# ultra-low-noise-psu-pos-v0001.net
KiCad netlist of a schematic drawn in EAGLE
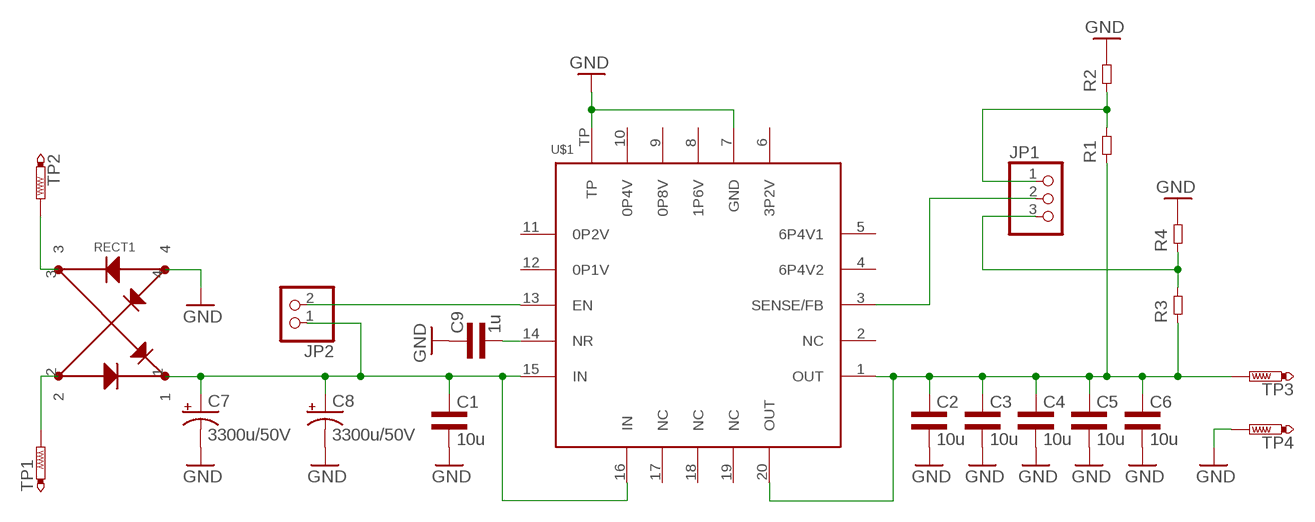
[diagram p0: schematic, sheet 1]

(export (version "E")
  (design (tool "Eeschema 10.0.6"))
  (components
    (comp (ref "C1")
      (value "10u")
      (footprint "eagle-import:0805L3")
      (libsource (lib "eagle-import") (part "CAP0805L3"))
    )
    (comp (ref "C2")
      (value "10u")
      (footprint "eagle-import:0805L3")
      (libsource (lib "eagle-import") (part "CAP0805L3"))
    )
    (comp (ref "C3")
      (value "10u")
      (footprint "eagle-import:0805L3")
      (libsource (lib "eagle-import") (part "CAP0805L3"))
    )
    (comp (ref "C4")
      (value "10u")
      (footprint "eagle-import:0805L3")
      (libsource (lib "eagle-import") (part "CAP0805L3"))
    )
    (comp (ref "C5")
      (value "10u")
      (footprint "eagle-import:0805L3")
      (libsource (lib "eagle-import") (part "CAP0805L3"))
    )
    (comp (ref "C6")
      (value "10u")
      (footprint "eagle-import:0805L3")
      (libsource (lib "eagle-import") (part "CAP0805L3"))
    )
    (comp (ref "C7")
      (value "3300u/50V")
      (footprint "eagle-import:E7,5-18")
      (libsource (lib "eagle-import") (part "CPOL-USE7.5-18"))
    )
    (comp (ref "C8")
      (value "3300u/50V")
      (footprint "eagle-import:E7,5-18")
      (libsource (lib "eagle-import") (part "CPOL-USE7.5-18"))
    )
    (comp (ref "C9")
      (value "1u")
      (footprint "eagle-import:0603L3")
      (libsource (lib "eagle-import") (part "CAP0603L3"))
    )
    (comp (ref "JP1")
      (value "PINHD-1X3")
      (footprint "eagle-import:1X03")
      (libsource (lib "eagle-import") (part "PINHD-1X3"))
    )
    (comp (ref "JP2")
      (value "PINHD-1X2")
      (footprint "eagle-import:1X02")
      (libsource (lib "eagle-import") (part "PINHD-1X2"))
    )
    (comp (ref "R1")
      (value "RES0603L3")
      (footprint "eagle-import:0603L3")
      (libsource (lib "eagle-import") (part "RES0603L3"))
    )
    (comp (ref "R2")
      (value "RES0603L3")
      (footprint "eagle-import:0603L3")
      (libsource (lib "eagle-import") (part "RES0603L3"))
    )
    (comp (ref "R3")
      (value "RES0603L3")
      (footprint "eagle-import:0603L3")
      (libsource (lib "eagle-import") (part "RES0603L3"))
    )
    (comp (ref "R4")
      (value "RES0603L3")
      (footprint "eagle-import:0603L3")
      (libsource (lib "eagle-import") (part "RES0603L3"))
    )
    (comp (ref "RECT1")
      (value "RECTIFIER_Z4GP206")
      (footprint "eagle-import:RECTIFIER_ABS-4")
      (libsource (lib "eagle-import") (part "RECTIFIER_Z4GP206"))
    )
    (comp (ref "TP1")
      (value "PTR1PAD1-20")
      (footprint "eagle-import:P1-20")
      (libsource (lib "eagle-import") (part "PTR1PAD1-20"))
    )
    (comp (ref "TP2")
      (value "PTR1PAD1-20")
      (footprint "eagle-import:P1-20")
      (libsource (lib "eagle-import") (part "PTR1PAD1-20"))
    )
    (comp (ref "TP3")
      (value "PTR1PAD1-20")
      (footprint "eagle-import:P1-20")
      (libsource (lib "eagle-import") (part "PTR1PAD1-20"))
    )
    (comp (ref "TP4")
      (value "PTR1PAD1-20")
      (footprint "eagle-import:P1-20")
      (libsource (lib "eagle-import") (part "PTR1PAD1-20"))
    )
    (comp (ref "U$1")
      (value "POWER-SUPPLY_POS_V1_TI_LDO_TPS7A4700")
      (footprint "eagle-import:POWER-SUPPLY_POS_V1_TI_LDO_VQFN-20")
      (libsource (lib "eagle-import") (part "POWER-SUPPLY_POS_V1_TI_LDO_TPS7A4700"))
    )
  )
  (nets
    (net (code "1") (name "GND") (class "Default")
      (node (ref "C1") (pin "2") (pinfunction "2_2") (pintype "bidirectional"))
      (node (ref "C2") (pin "2") (pinfunction "2_2") (pintype "bidirectional"))
      (node (ref "C3") (pin "2") (pinfunction "2_2") (pintype "bidirectional"))
      (node (ref "C4") (pin "2") (pinfunction "2_2") (pintype "bidirectional"))
      (node (ref "C5") (pin "2") (pinfunction "2_2") (pintype "bidirectional"))
      (node (ref "C6") (pin "2") (pinfunction "2_2") (pintype "bidirectional"))
      (node (ref "C7") (pin "-") (pinfunction "-_-") (pintype "passive"))
      (node (ref "C8") (pin "-") (pinfunction "-_-") (pintype "passive"))
      (node (ref "C9") (pin "P$1") (pinfunction "1_P$1") (pintype "bidirectional"))
      (node (ref "R2") (pin "P$2") (pinfunction "2_P$2") (pintype "bidirectional"))
      (node (ref "R4") (pin "P$2") (pinfunction "2_P$2") (pintype "bidirectional"))
      (node (ref "RECT1") (pin "4") (pinfunction "4_4") (pintype "bidirectional"))
      (node (ref "TP4") (pin "TP") (pinfunction "TP_TP") (pintype "input"))
      (node (ref "U$1") (pin "7") (pinfunction "GND_7") (pintype "bidirectional"))
      (node (ref "U$1") (pin "TP") (pinfunction "TP_TP") (pintype "bidirectional"))
    )
    (net (code "2") (name "Net-(C1-Pad1)") (class "Default")
      (node (ref "C1") (pin "1") (pinfunction "1_1") (pintype "bidirectional"))
      (node (ref "C7") (pin "+") (pinfunction "+_+") (pintype "passive"))
      (node (ref "C8") (pin "+") (pinfunction "+_+") (pintype "passive"))
      (node (ref "JP2") (pin "1") (pinfunction "1_1") (pintype "passive"))
      (node (ref "RECT1") (pin "1") (pinfunction "1_1") (pintype "bidirectional"))
      (node (ref "U$1") (pin "15") (pinfunction "IN_15") (pintype "bidirectional"))
      (node (ref "U$1") (pin "16") (pinfunction "IN_16") (pintype "bidirectional"))
    )
    (net (code "3") (name "Net-(C9-2)") (class "Default")
      (node (ref "C9") (pin "P$2") (pinfunction "2_P$2") (pintype "bidirectional"))
      (node (ref "U$1") (pin "14") (pinfunction "NR_14") (pintype "bidirectional"))
    )
    (net (code "4") (name "Net-(R1-1)") (class "Default")
      (node (ref "C2") (pin "1") (pinfunction "1_1") (pintype "bidirectional"))
      (node (ref "C3") (pin "1") (pinfunction "1_1") (pintype "bidirectional"))
      (node (ref "C4") (pin "1") (pinfunction "1_1") (pintype "bidirectional"))
      (node (ref "C5") (pin "1") (pinfunction "1_1") (pintype "bidirectional"))
      (node (ref "C6") (pin "1") (pinfunction "1_1") (pintype "bidirectional"))
      (node (ref "R1") (pin "P$1") (pinfunction "1_P$1") (pintype "bidirectional"))
      (node (ref "R3") (pin "P$1") (pinfunction "1_P$1") (pintype "bidirectional"))
      (node (ref "TP3") (pin "TP") (pinfunction "TP_TP") (pintype "input"))
      (node (ref "U$1") (pin "1") (pinfunction "OUT_1") (pintype "bidirectional"))
      (node (ref "U$1") (pin "20") (pinfunction "OUT_20") (pintype "bidirectional"))
    )
    (net (code "5") (name "Net-(R1-2)") (class "Default")
      (node (ref "JP1") (pin "1") (pinfunction "1_1") (pintype "passive"))
      (node (ref "R1") (pin "P$2") (pinfunction "2_P$2") (pintype "bidirectional"))
      (node (ref "R2") (pin "P$1") (pinfunction "1_P$1") (pintype "bidirectional"))
    )
    (net (code "6") (name "Net-(R3-2)") (class "Default")
      (node (ref "JP1") (pin "3") (pinfunction "3_3") (pintype "passive"))
      (node (ref "R3") (pin "P$2") (pinfunction "2_P$2") (pintype "bidirectional"))
      (node (ref "R4") (pin "P$1") (pinfunction "1_P$1") (pintype "bidirectional"))
    )
    (net (code "7") (name "Net-(RECT1-Pad2)") (class "Default")
      (node (ref "RECT1") (pin "2") (pinfunction "2_2") (pintype "bidirectional"))
      (node (ref "TP1") (pin "TP") (pinfunction "TP_TP") (pintype "input"))
    )
    (net (code "8") (name "Net-(RECT1-Pad3)") (class "Default")
      (node (ref "RECT1") (pin "3") (pinfunction "3_3") (pintype "bidirectional"))
      (node (ref "TP2") (pin "TP") (pinfunction "TP_TP") (pintype "input"))
    )
    (net (code "9") (name "Net-(U$1-EN)") (class "Default")
      (node (ref "JP2") (pin "2") (pinfunction "2_2") (pintype "passive"))
      (node (ref "U$1") (pin "13") (pinfunction "EN_13") (pintype "bidirectional"))
    )
    (net (code "10") (name "Net-(U$1-SENSE{slash}FB)") (class "Default")
      (node (ref "JP1") (pin "2") (pinfunction "2_2") (pintype "passive"))
      (node (ref "U$1") (pin "3") (pinfunction "SENSE/FB_3") (pintype "bidirectional"))
    )
    (net (code "11") (name "unconnected-(U$1-0P1V-Pad12)") (class "Default")
      (node (ref "U$1") (pin "12") (pinfunction "0P1V_12") (pintype "bidirectional"))
    )
    (net (code "12") (name "unconnected-(U$1-0P2V-Pad11)") (class "Default")
      (node (ref "U$1") (pin "11") (pinfunction "0P2V_11") (pintype "bidirectional"))
    )
    (net (code "13") (name "unconnected-(U$1-0P4V-Pad10)") (class "Default")
      (node (ref "U$1") (pin "10") (pinfunction "0P4V_10") (pintype "bidirectional"))
    )
    (net (code "14") (name "unconnected-(U$1-0P8V-Pad9)") (class "Default")
      (node (ref "U$1") (pin "9") (pinfunction "0P8V_9") (pintype "bidirectional"))
    )
    (net (code "15") (name "unconnected-(U$1-1P6V-Pad8)") (class "Default")
      (node (ref "U$1") (pin "8") (pinfunction "1P6V_8") (pintype "bidirectional"))
    )
    (net (code "16") (name "unconnected-(U$1-3P2V-Pad6)") (class "Default")
      (node (ref "U$1") (pin "6") (pinfunction "3P2V_6") (pintype "bidirectional"))
    )
    (net (code "17") (name "unconnected-(U$1-6P4V1-Pad5)") (class "Default")
      (node (ref "U$1") (pin "5") (pinfunction "6P4V1_5") (pintype "bidirectional"))
    )
    (net (code "18") (name "unconnected-(U$1-6P4V2-Pad4)") (class "Default")
      (node (ref "U$1") (pin "4") (pinfunction "6P4V2_4") (pintype "bidirectional"))
    )
    (net (code "19") (name "unconnected-(U$1-NC-Pad2)") (class "Default")
      (node (ref "U$1") (pin "2") (pinfunction "NC_2") (pintype "bidirectional"))
    )
    (net (code "20") (name "unconnected-(U$1-NC-Pad17)") (class "Default")
      (node (ref "U$1") (pin "17") (pinfunction "NC_17") (pintype "bidirectional"))
    )
    (net (code "21") (name "unconnected-(U$1-NC-Pad18)") (class "Default")
      (node (ref "U$1") (pin "18") (pinfunction "NC_18") (pintype "bidirectional"))
    )
    (net (code "22") (name "unconnected-(U$1-NC-Pad19)") (class "Default")
      (node (ref "U$1") (pin "19") (pinfunction "NC_19") (pintype "bidirectional"))
    )
  )
)
